# Arduino-DRA818V-TX.net
KiCad netlist of a schematic drawn in EAGLE
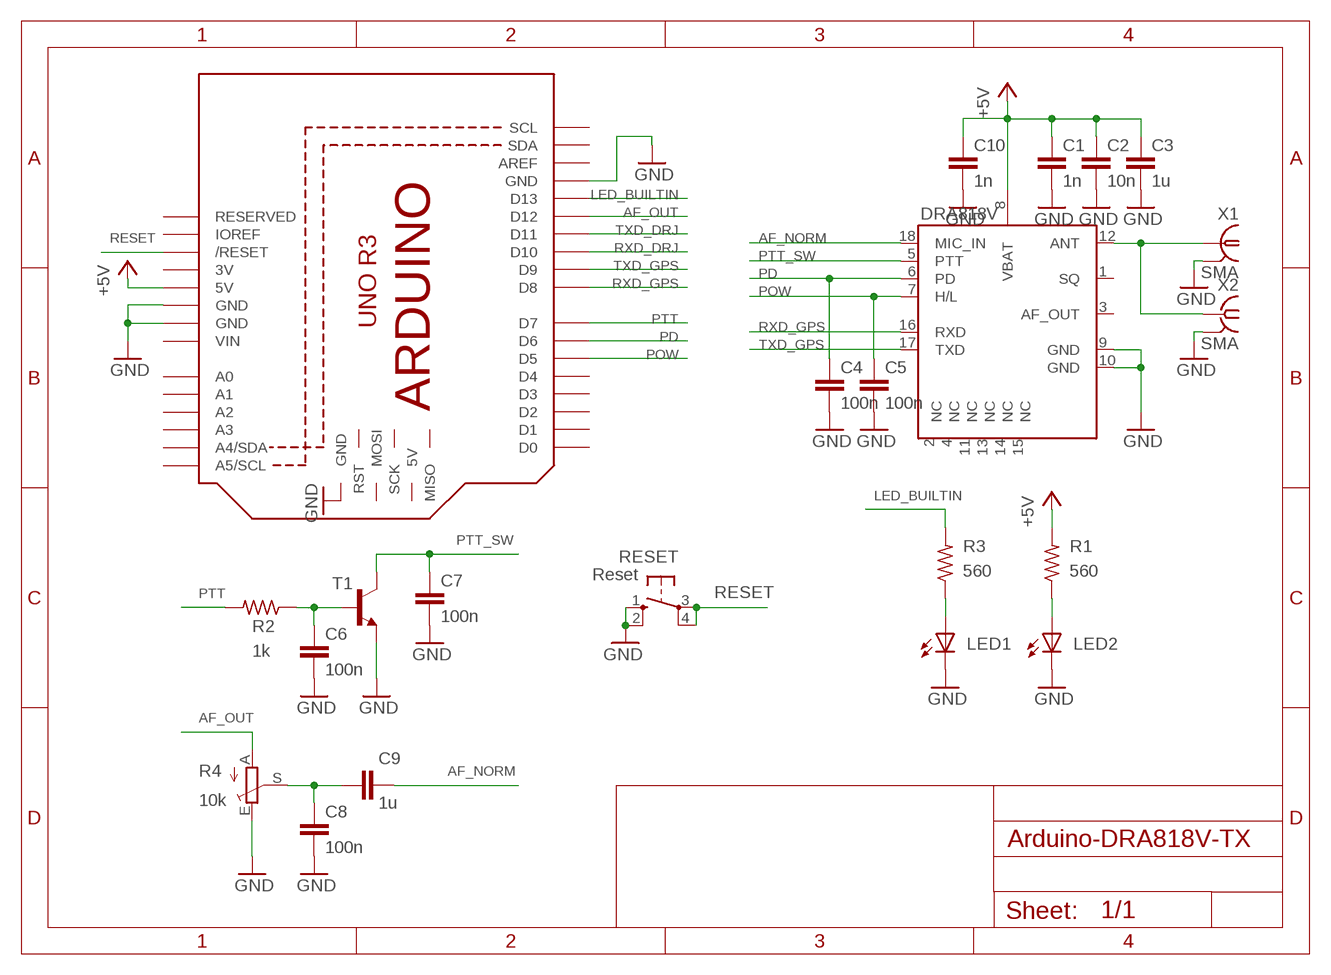
[diagram p0: schematic, sheet 1]

(export (version "E")
  (design (tool "Eeschema 10.0.6"))
  (components
    (comp (ref "C1")
      (value "1n")
      (footprint "eagle-import:C1206")
      (libsource (lib "eagle-import") (part "C-EUC1206"))
    )
    (comp (ref "C2")
      (value "10n")
      (footprint "eagle-import:C1206")
      (libsource (lib "eagle-import") (part "C-EUC1206"))
    )
    (comp (ref "C3")
      (value "1u")
      (footprint "eagle-import:C1206")
      (libsource (lib "eagle-import") (part "C-EUC1206"))
    )
    (comp (ref "C4")
      (value "100n")
      (footprint "eagle-import:C1206")
      (libsource (lib "eagle-import") (part "C-EUC1206"))
    )
    (comp (ref "C5")
      (value "100n")
      (footprint "eagle-import:C1206")
      (libsource (lib "eagle-import") (part "C-EUC1206"))
    )
    (comp (ref "C6")
      (value "100n")
      (footprint "eagle-import:C1206")
      (libsource (lib "eagle-import") (part "C-EUC1206"))
    )
    (comp (ref "C7")
      (value "100n")
      (footprint "eagle-import:C1206")
      (libsource (lib "eagle-import") (part "C-EUC1206"))
    )
    (comp (ref "C8")
      (value "100n")
      (footprint "eagle-import:C1206")
      (libsource (lib "eagle-import") (part "C-EUC1206"))
    )
    (comp (ref "C9")
      (value "1u")
      (footprint "eagle-import:C1206")
      (libsource (lib "eagle-import") (part "C-EUC1206"))
    )
    (comp (ref "C10")
      (value "1n")
      (footprint "eagle-import:C1206")
      (libsource (lib "eagle-import") (part "C-EUC1206"))
    )
    (comp (ref "DRA818V")
      (value "DRA818A")
      (footprint "eagle-import:DRA818A")
      (libsource (lib "eagle-import") (part "DRA818A"))
    )
    (comp (ref "LED1")
      (value "LED3MM")
      (footprint "eagle-import:LED3MM")
      (libsource (lib "eagle-import") (part "LED3MM"))
    )
    (comp (ref "LED2")
      (value "LED3MM")
      (footprint "eagle-import:LED3MM")
      (libsource (lib "eagle-import") (part "LED3MM"))
    )
    (comp (ref "M1")
      (value "ARDUINO_R3_ICSP")
      (footprint "eagle-import:ARDUINOR3_ICSP")
      (libsource (lib "eagle-import") (part "ARDUINO_R3_ICSP"))
    )
    (comp (ref "R1")
      (value "560")
      (footprint "eagle-import:R1206")
      (libsource (lib "eagle-import") (part "R-US_R1206"))
    )
    (comp (ref "R2")
      (value "1k")
      (footprint "eagle-import:R1206")
      (libsource (lib "eagle-import") (part "R-US_R1206"))
    )
    (comp (ref "R3")
      (value "560")
      (footprint "eagle-import:R1206")
      (libsource (lib "eagle-import") (part "R-US_R1206"))
    )
    (comp (ref "R4")
      (value "10k")
      (footprint "eagle-import:CA6V")
      (libsource (lib "eagle-import") (part "TRIM_EU-CA6V"))
    )
    (comp (ref "RESET")
      (value "Reset")
      (footprint "eagle-import:B3F-10XX")
      (fields (field (name "MPN") "B3F-1000"))
      (libsource (lib "eagle-import") (part "10-XX"))
    )
    (comp (ref "T1")
      (value "MMBT3904LT1-NPN-SOT23-BEC")
      (footprint "eagle-import:SOT23-BEC")
      (libsource (lib "eagle-import") (part "-NPN-SOT23-BECMMBT3904LT1"))
    )
    (comp (ref "X1")
      (value "SMA")
      (footprint "eagle-import:LTI-SASF54GT")
      (libsource (lib "eagle-import") (part "LTI-SASF54GT"))
    )
    (comp (ref "X2")
      (value "SMA")
      (footprint "eagle-import:J502-ND-142-0701-801_806")
      (fields (field (name "MF") "JOHNSON COMPONENTS") (field (name "MPN") "142-0701-801"))
      (libsource (lib "eagle-import") (part "SMA-142-0701-801/806"))
    )
  )
  (nets
    (net (code "1") (name "+5V") (class "Default")
      (node (ref "C1") (pin "1") (pinfunction "1_1") (pintype "passive"))
      (node (ref "C10") (pin "1") (pinfunction "1_1") (pintype "passive"))
      (node (ref "C2") (pin "1") (pinfunction "1_1") (pintype "passive"))
      (node (ref "C3") (pin "1") (pinfunction "1_1") (pintype "passive"))
      (node (ref "DRA818V") (pin "8") (pinfunction "VBAT_8") (pintype "bidirectional"))
      (node (ref "M1") (pin "5V") (pinfunction "5V_5V") (pintype "power_in"))
      (node (ref "R1") (pin "2") (pinfunction "2_2") (pintype "passive"))
    )
    (net (code "2") (name "/3V") (class "Default")
      (node (ref "M1") (pin "3V") (pinfunction "3V_3V") (pintype "power_in"))
    )
    (net (code "3") (name "/AF_NORM") (class "Default")
      (node (ref "C9") (pin "2") (pinfunction "2_2") (pintype "passive"))
      (node (ref "DRA818V") (pin "18") (pinfunction "MIC_IN_18") (pintype "bidirectional"))
    )
    (net (code "4") (name "/AF_OUT") (class "Default")
      (node (ref "M1") (pin "D12") (pinfunction "D12_D12") (pintype "bidirectional"))
      (node (ref "R4") (pin "A") (pinfunction "A_A") (pintype "passive"))
    )
    (net (code "5") (name "/LED_BUILTIN") (class "Default")
      (node (ref "M1") (pin "D13") (pinfunction "D13_D13") (pintype "bidirectional"))
      (node (ref "R3") (pin "2") (pinfunction "2_2") (pintype "passive"))
    )
    (net (code "6") (name "/PD") (class "Default")
      (node (ref "C4") (pin "1") (pinfunction "1_1") (pintype "passive"))
      (node (ref "DRA818V") (pin "6") (pinfunction "PD_6") (pintype "bidirectional"))
      (node (ref "M1") (pin "D6") (pinfunction "D6_D6") (pintype "bidirectional"))
    )
    (net (code "7") (name "/POW") (class "Default")
      (node (ref "C5") (pin "1") (pinfunction "1_1") (pintype "passive"))
      (node (ref "DRA818V") (pin "7") (pinfunction "H/L_7") (pintype "bidirectional"))
      (node (ref "M1") (pin "D5") (pinfunction "D5_D5") (pintype "bidirectional"))
    )
    (net (code "8") (name "/PTT") (class "Default")
      (node (ref "M1") (pin "D7") (pinfunction "D7_D7") (pintype "bidirectional"))
      (node (ref "R2") (pin "2") (pinfunction "2_2") (pintype "passive"))
    )
    (net (code "9") (name "/PTT_SW") (class "Default")
      (node (ref "C7") (pin "1") (pinfunction "1_1") (pintype "passive"))
      (node (ref "DRA818V") (pin "5") (pinfunction "PTT_5") (pintype "bidirectional"))
      (node (ref "T1") (pin "C") (pinfunction "C_C") (pintype "passive"))
    )
    (net (code "10") (name "/RESET") (class "Default")
      (node (ref "M1") (pin "RESET") (pinfunction "/RESET_RESET") (pintype "bidirectional"))
      (node (ref "RESET") (pin "3") (pinfunction "P_3") (pintype "passive"))
      (node (ref "RESET") (pin "4") (pinfunction "P1_4") (pintype "passive"))
    )
    (net (code "11") (name "/RXD_DRJ") (class "Default")
      (node (ref "M1") (pin "D10") (pinfunction "D10_D10") (pintype "bidirectional"))
    )
    (net (code "12") (name "/RXD_GPS") (class "Default")
      (node (ref "DRA818V") (pin "16") (pinfunction "RXD_16") (pintype "bidirectional"))
      (node (ref "M1") (pin "D8") (pinfunction "D8_D8") (pintype "bidirectional"))
    )
    (net (code "13") (name "/TXD_DRJ") (class "Default")
      (node (ref "M1") (pin "D11") (pinfunction "D11_D11") (pintype "bidirectional"))
    )
    (net (code "14") (name "/TXD_GPS") (class "Default")
      (node (ref "DRA818V") (pin "17") (pinfunction "TXD_17") (pintype "bidirectional"))
      (node (ref "M1") (pin "D9") (pinfunction "D9_D9") (pintype "bidirectional"))
    )
    (net (code "15") (name "/VIN") (class "Default")
      (node (ref "M1") (pin "VIN") (pinfunction "VIN_VIN") (pintype "power_in"))
    )
    (net (code "16") (name "GND") (class "Default")
      (node (ref "C1") (pin "2") (pinfunction "2_2") (pintype "passive"))
      (node (ref "C10") (pin "2") (pinfunction "2_2") (pintype "passive"))
      (node (ref "C2") (pin "2") (pinfunction "2_2") (pintype "passive"))
      (node (ref "C3") (pin "2") (pinfunction "2_2") (pintype "passive"))
      (node (ref "C4") (pin "2") (pinfunction "2_2") (pintype "passive"))
      (node (ref "C5") (pin "2") (pinfunction "2_2") (pintype "passive"))
      (node (ref "C6") (pin "2") (pinfunction "2_2") (pintype "passive"))
      (node (ref "C7") (pin "2") (pinfunction "2_2") (pintype "passive"))
      (node (ref "C8") (pin "2") (pinfunction "2_2") (pintype "passive"))
      (node (ref "DRA818V") (pin "10") (pinfunction "GND_10") (pintype "bidirectional"))
      (node (ref "DRA818V") (pin "9") (pinfunction "GND_9") (pintype "bidirectional"))
      (node (ref "LED1") (pin "K") (pinfunction "C_K") (pintype "passive"))
      (node (ref "LED2") (pin "K") (pinfunction "C_K") (pintype "passive"))
      (node (ref "M1") (pin "GND") (pinfunction "GND_GND") (pintype "power_in"))
      (node (ref "M1") (pin "GND@1") (pinfunction "GND_GND@1") (pintype "power_in"))
      (node (ref "M1") (pin "GND@2") (pinfunction "GND_GND@2") (pintype "passive"))
      (node (ref "M1") (pin "GND@3") (pinfunction "GND_GND@3") (pintype "power_in"))
      (node (ref "R4") (pin "E") (pinfunction "E_E") (pintype "passive"))
      (node (ref "RESET") (pin "1") (pinfunction "S_1") (pintype "passive"))
      (node (ref "RESET") (pin "2") (pinfunction "S1_2") (pintype "passive"))
      (node (ref "T1") (pin "E") (pinfunction "E_E") (pintype "passive"))
      (node (ref "X1") (pin "2") (pinfunction "2_2") (pintype "passive"))
      (node (ref "X1") (pin "3") (pinfunction "2_3") (pintype "passive"))
      (node (ref "X1") (pin "4") (pinfunction "2_4") (pintype "passive"))
      (node (ref "X1") (pin "5") (pinfunction "2_5") (pintype "passive"))
      (node (ref "X2") (pin "G@1") (pinfunction "2_G@1") (pintype "passive"))
      (node (ref "X2") (pin "G@2") (pinfunction "2_G@2") (pintype "passive"))
      (node (ref "X2") (pin "G@3") (pinfunction "2_G@3") (pintype "passive"))
      (node (ref "X2") (pin "G@4") (pinfunction "2_G@4") (pintype "passive"))
    )
    (net (code "17") (name "Net-(C6-Pad1)") (class "Default")
      (node (ref "C6") (pin "1") (pinfunction "1_1") (pintype "passive"))
      (node (ref "R2") (pin "1") (pinfunction "1_1") (pintype "passive"))
      (node (ref "T1") (pin "B") (pinfunction "B_B") (pintype "passive"))
    )
    (net (code "18") (name "Net-(C8-Pad1)") (class "Default")
      (node (ref "C8") (pin "1") (pinfunction "1_1") (pintype "passive"))
      (node (ref "C9") (pin "1") (pinfunction "1_1") (pintype "passive"))
      (node (ref "R4") (pin "S") (pinfunction "S_S") (pintype "passive"))
    )
    (net (code "19") (name "Net-(DRA818V-ANT)") (class "Default")
      (node (ref "DRA818V") (pin "12") (pinfunction "ANT_12") (pintype "bidirectional"))
      (node (ref "X1") (pin "1") (pinfunction "1_1") (pintype "passive"))
      (node (ref "X2") (pin "1") (pinfunction "1_1") (pintype "passive"))
    )
    (net (code "20") (name "Net-(LED1-PadA)") (class "Default")
      (node (ref "LED1") (pin "A") (pinfunction "A_A") (pintype "passive"))
      (node (ref "R3") (pin "1") (pinfunction "1_1") (pintype "passive"))
    )
    (net (code "21") (name "Net-(LED2-PadA)") (class "Default")
      (node (ref "LED2") (pin "A") (pinfunction "A_A") (pintype "passive"))
      (node (ref "R1") (pin "1") (pinfunction "1_1") (pintype "passive"))
    )
    (net (code "22") (name "unconnected-(DRA818V-AF_OUT-Pad3)") (class "Default")
      (node (ref "DRA818V") (pin "3") (pinfunction "AF_OUT_3") (pintype "bidirectional"))
    )
    (net (code "23") (name "unconnected-(DRA818V-NC-Pad2)") (class "Default")
      (node (ref "DRA818V") (pin "2") (pinfunction "NC_2") (pintype "bidirectional"))
    )
    (net (code "24") (name "unconnected-(DRA818V-NC-Pad4)") (class "Default")
      (node (ref "DRA818V") (pin "4") (pinfunction "NC_4") (pintype "bidirectional"))
    )
    (net (code "25") (name "unconnected-(DRA818V-NC-Pad11)") (class "Default")
      (node (ref "DRA818V") (pin "11") (pinfunction "NC_11") (pintype "bidirectional"))
    )
    (net (code "26") (name "unconnected-(DRA818V-NC-Pad13)") (class "Default")
      (node (ref "DRA818V") (pin "13") (pinfunction "NC_13") (pintype "bidirectional"))
    )
    (net (code "27") (name "unconnected-(DRA818V-NC-Pad14)") (class "Default")
      (node (ref "DRA818V") (pin "14") (pinfunction "NC_14") (pintype "bidirectional"))
    )
    (net (code "28") (name "unconnected-(DRA818V-NC-Pad15)") (class "Default")
      (node (ref "DRA818V") (pin "15") (pinfunction "NC_15") (pintype "bidirectional"))
    )
    (net (code "29") (name "unconnected-(DRA818V-SQ-Pad1)") (class "Default")
      (node (ref "DRA818V") (pin "1") (pinfunction "SQ_1") (pintype "bidirectional"))
    )
    (net (code "30") (name "unconnected-(M1-5V-Pad5V_ICSP)") (class "Default")
      (node (ref "M1") (pin "5V_ICSP") (pinfunction "5V_5V_ICSP") (pintype "passive"))
    )
    (net (code "31") (name "unconnected-(M1-A4{slash}SDA-PadA4)") (class "Default")
      (node (ref "M1") (pin "A4") (pinfunction "A4/SDA_A4") (pintype "bidirectional"))
    )
    (net (code "32") (name "unconnected-(M1-A5{slash}SCL-PadA5)") (class "Default")
      (node (ref "M1") (pin "A5") (pinfunction "A5/SCL_A5") (pintype "bidirectional"))
    )
    (net (code "33") (name "unconnected-(M1-PadA0)") (class "Default")
      (node (ref "M1") (pin "A0") (pinfunction "A0_A0") (pintype "bidirectional"))
    )
    (net (code "34") (name "unconnected-(M1-PadA1)") (class "Default")
      (node (ref "M1") (pin "A1") (pinfunction "A1_A1") (pintype "bidirectional"))
    )
    (net (code "35") (name "unconnected-(M1-PadA2)") (class "Default")
      (node (ref "M1") (pin "A2") (pinfunction "A2_A2") (pintype "bidirectional"))
    )
    (net (code "36") (name "unconnected-(M1-PadA3)") (class "Default")
      (node (ref "M1") (pin "A3") (pinfunction "A3_A3") (pintype "bidirectional"))
    )
    (net (code "37") (name "unconnected-(M1-PadAREF)") (class "Default")
      (node (ref "M1") (pin "AREF") (pinfunction "AREF_AREF") (pintype "bidirectional"))
    )
    (net (code "38") (name "unconnected-(M1-PadD0)") (class "Default")
      (node (ref "M1") (pin "D0") (pinfunction "D0_D0") (pintype "bidirectional"))
    )
    (net (code "39") (name "unconnected-(M1-PadD1)") (class "Default")
      (node (ref "M1") (pin "D1") (pinfunction "D1_D1") (pintype "bidirectional"))
    )
    (net (code "40") (name "unconnected-(M1-PadD2)") (class "Default")
      (node (ref "M1") (pin "D2") (pinfunction "D2_D2") (pintype "bidirectional"))
    )
    (net (code "41") (name "unconnected-(M1-PadD3)") (class "Default")
      (node (ref "M1") (pin "D3") (pinfunction "D3_D3") (pintype "bidirectional"))
    )
    (net (code "42") (name "unconnected-(M1-PadD4)") (class "Default")
      (node (ref "M1") (pin "D4") (pinfunction "D4_D4") (pintype "bidirectional"))
    )
    (net (code "43") (name "unconnected-(M1-PadIOREF)") (class "Default")
      (node (ref "M1") (pin "IOREF") (pinfunction "IOREF_IOREF") (pintype "output"))
    )
    (net (code "44") (name "unconnected-(M1-PadMISO)") (class "Default")
      (node (ref "M1") (pin "MISO") (pinfunction "MISO_MISO") (pintype "passive"))
    )
    (net (code "45") (name "unconnected-(M1-PadMOSI)") (class "Default")
      (node (ref "M1") (pin "MOSI") (pinfunction "MOSI_MOSI") (pintype "passive"))
    )
    (net (code "46") (name "unconnected-(M1-PadRESERVED)") (class "Default")
      (node (ref "M1") (pin "RESERVED") (pinfunction "RESERVED_RESERVED") (pintype "no_connect"))
    )
    (net (code "47") (name "unconnected-(M1-PadSCK)") (class "Default")
      (node (ref "M1") (pin "SCK") (pinfunction "SCK_SCK") (pintype "passive"))
    )
    (net (code "48") (name "unconnected-(M1-PadSCL)") (class "Default")
      (node (ref "M1") (pin "SCL") (pinfunction "SCL_SCL") (pintype "bidirectional"))
    )
    (net (code "49") (name "unconnected-(M1-PadSDA)") (class "Default")
      (node (ref "M1") (pin "SDA") (pinfunction "SDA_SDA") (pintype "bidirectional"))
    )
    (net (code "50") (name "unconnected-(M1-RST-PadRESET_ICSP)") (class "Default")
      (node (ref "M1") (pin "RESET_ICSP") (pinfunction "RST_RESET_ICSP") (pintype "passive"))
    )
  )
)
